# Steering_Wheel.net
KiCad netlist of a schematic drawn in Altium Designer
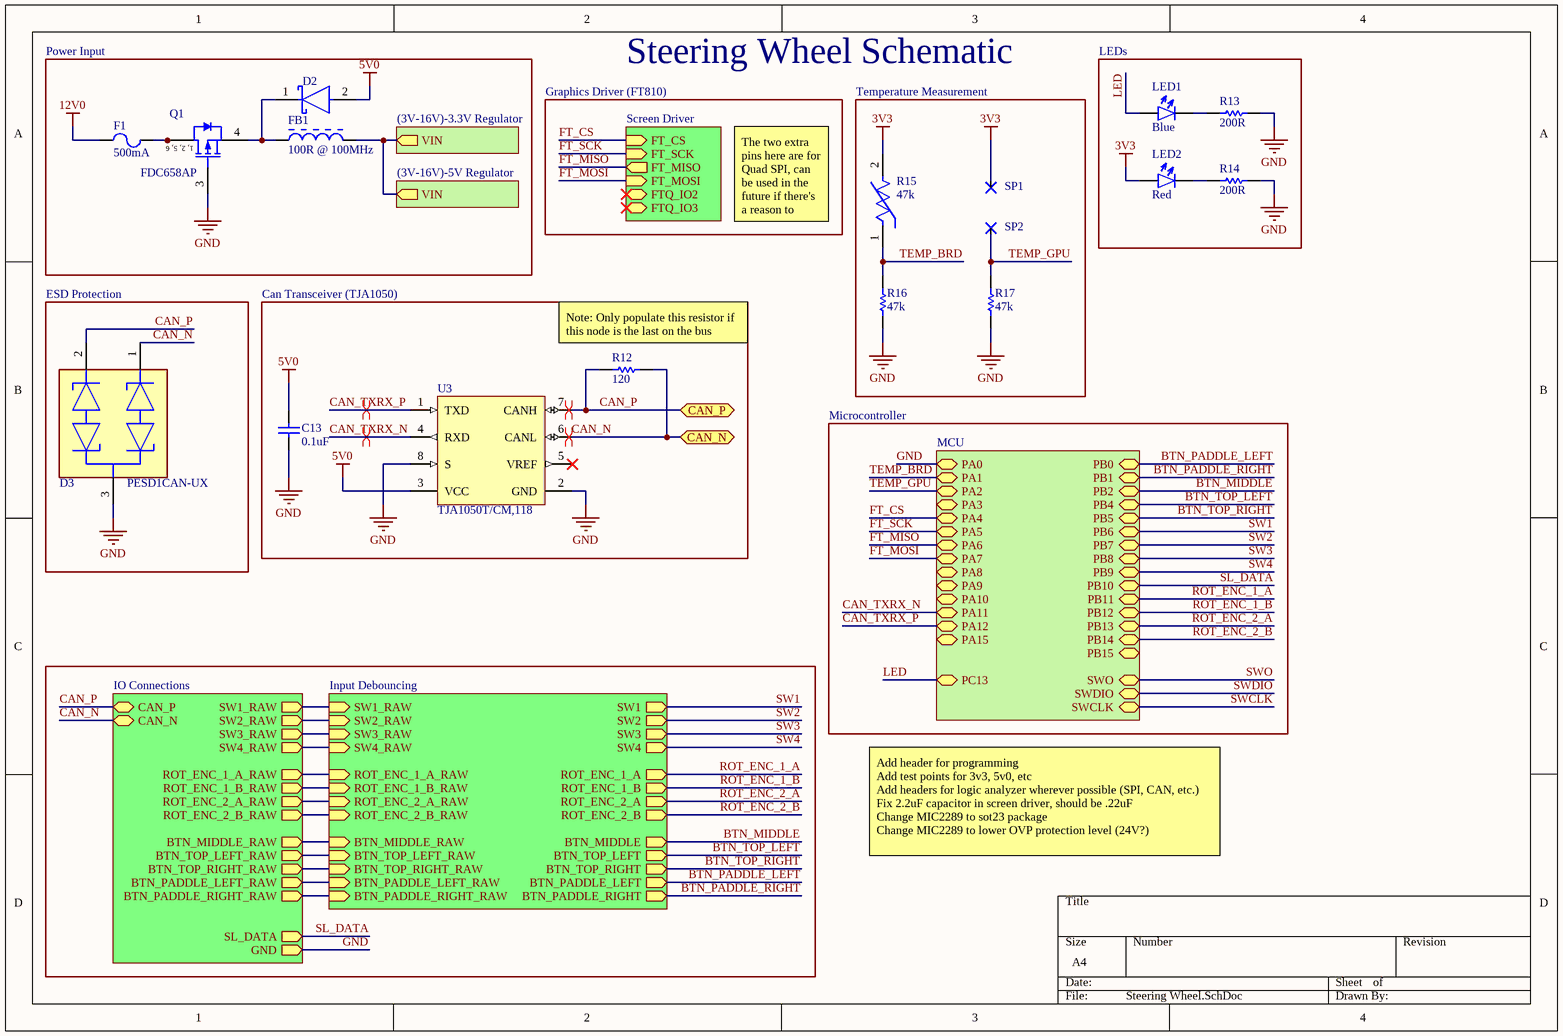
[diagram p0: Steering Wheel.SchDoc]

(export (version "E")
  (design (tool "Eeschema 10.0.6"))
  (components
    (comp (ref "C13")
      (value "0.1uF")
      (footprint "CAPC2013X88X50NL20T25")
      (fields
        (field (name "PART NUMBER") "C0805C104K5RACTU")
        (field (name "MANUFACTURER") "Kemet")
        (field (name "TOLERANCE") "10%")
      )
      (libsource (lib "Altium Content Vault") (part "CAP"))
    )
    (comp (ref "D2")
      (value "~")
      (footprint "FP-95400-MFG")
      (description "DIODE SCHOTTKY 40V 3A DO214AC")
      (fields
        (field (name "MANUFACTURER PART NUMBER") "SSA34-E3/61T")
        (field (name "OCTOPART") "https://octopart.com/ssa34-e3%2F61t-vishay-39552934")
      )
      (libsource (lib "Altium Content Vault") (part "1d6ec82d83fb6aee721767c19dac4b9"))
    )
    (comp (ref "D3")
      (value "PESD1CAN-UX")
      (footprint "FP-SOT323-MFG")
      (description "TVS DIODE 24V 50V SC70-3")
      (fields (field (name "MANUFACTURER") "Nexperia"))
      (libsource (lib "Altium Content Vault") (part "04d57993b6b7b0f5b3c95ba4f97dea0"))
    )
    (comp (ref "F1")
      (value "500mA")
      (footprint "LFUS-0452_V")
      (description "NANO2(R) Slo-Blo(R) Fuse, 0.5 A, 125 V, -55 to 125 degC, 2-Pin SMD, RoHS, Tape and Reel")
      (fields
        (field (name "MANUFACTURER") "Littelfuse")
        (field (name "MANUFACTURER PART NUMBER") "0452.500MRL")
      )
      (libsource (lib "Altium Content Vault") (part "FUSE-2"))
    )
    (comp (ref "FB1")
      (value "100R @ 100MHz")
      (footprint "MURA-BLM18PG_KG-B25-CHIP-2_V1")
      (fields
        (field (name "PARTNUMBER") "BLM18PG121SN1D")
        (field (name "MANUFACTURER") "Murata")
        (field (name "TOLERANCE") "25%")
      )
      (libsource (lib "Altium Content Vault") (part "MURA-FB-2"))
    )
    (comp (ref "LED1")
      (value "Blue")
      (footprint "Dummy Parts:0805")
      (libsource (lib "Dummy Parts") (part "LED"))
    )
    (comp (ref "LED2")
      (value "Red")
      (footprint "Dummy Parts:0805")
      (libsource (lib "Dummy Parts") (part "LED"))
    )
    (comp (ref "Q1")
      (value "FDC658AP")
      (footprint "FAIR-SOT23-6_V")
      (fields (field (name "MANUFACTURER") "Fairchild Semiconductor"))
      (libsource (lib "Altium Content Vault") (part "PEMOS-DDGSDD-6"))
    )
    (comp (ref "R12")
      (value "120")
      (footprint "RESC2013X70X40NL20T20")
      (description "Chip Resistor, 120 Ohm, +/- 1%, 0.125 W, -55 to 155 degC, 0805 (2012 Metric), RoHS, Tape and Reel")
      (fields
        (field (name "MANUFACTURER") "Panasonic")
        (field (name "MANUFACTURER PART NUMBER") "ERJ-6ENF1200V")
      )
      (libsource (lib "Altium Content Vault") (part "RES-2"))
    )
    (comp (ref "R13")
      (value "200R")
      (footprint "0805")
      (description "Resistor; Thick Film; Res 200 Ohms; Pwr-Rtg 0.125 W; Tol 1%; SMT; 0805; Cut Tape")
      (fields
        (field (name "MANUFACTURER") "Panasonic")
        (field (name "MANUFACTURER PART NUMBER") "ERJ-6ENF2000V")
      )
      (libsource (lib "Dummy Parts") (part "Resistor"))
    )
    (comp (ref "R14")
      (value "200R")
      (footprint "0805")
      (description "Resistor; Thick Film; Res 200 Ohms; Pwr-Rtg 0.125 W; Tol 1%; SMT; 0805; Cut Tape")
      (fields
        (field (name "MANUFACTURER") "Panasonic")
        (field (name "MANUFACTURER PART NUMBER") "ERJ-6ENF2000V")
      )
      (libsource (lib "Dummy Parts") (part "Resistor"))
    )
    (comp (ref "R15")
      (value "47k")
      (footprint "FP-NCP21-0_2-IPC_B")
      (description "THERMISTOR NTC 47KOHM 4050K 0805")
      (fields (field (name "TOLERANCE") "5%") (field (name "MANUFACTURER") "Murata"))
      (libsource (lib "Altium Content Vault") (part "3b148a6ebabc5fb4d708a66c052d352"))
    )
    (comp (ref "R16")
      (value "47k")
      (footprint "RESC2013X70X40ML20T20")
      (fields
        (field (name "MANUFACTURER") "Panasonic")
        (field (name "PART NUMBER") "ERJ6ENF4702V")
        (field (name "MANUFACTURER PART NUMBER") "ERJ-6ENF4702V")
      )
      (libsource (lib "Altium Content Vault") (part "RES"))
    )
    (comp (ref "R17")
      (value "47k")
      (footprint "RESC2013X70X40ML20T20")
      (fields
        (field (name "MANUFACTURER") "Panasonic")
        (field (name "PART NUMBER") "ERJ6ENF4702V")
        (field (name "MANUFACTURER PART NUMBER") "ERJ-6ENF4702V")
      )
      (libsource (lib "Altium Content Vault") (part "RES"))
    )
    (comp (ref "SP1")
      (value "Rectangular")
      (footprint "2.5x5mm")
      (libsource (lib "Solder Pads") (part "Rectangular"))
    )
    (comp (ref "SP2")
      (value "Rectangular")
      (footprint "2.5x5mm")
      (libsource (lib "Solder Pads") (part "Rectangular"))
    )
    (comp (ref "U3")
      (value "TJA1050T/CM,118")
      (footprint "NXP-SOT96-1_M")
      (fields (field (name "MANUFACTURER") "NXP Semiconductors"))
      (libsource (lib "Altium Content Vault") (part "NXP-TJA1050-8"))
    )
  )
  (nets
    (net (code "11") (name "/CAN_N") (class "Default")
      (node (ref "D3") (pin "1") (pinfunction "cathode_1_1") (pintype "passive"))
      (node (ref "R12") (pin "2") (pinfunction "2_2") (pintype "passive"))
      (node (ref "U3") (pin "6") (pinfunction "CANL_6") (pintype "bidirectional"))
    )
    (net (code "12") (name "/CAN_P") (class "Default")
      (node (ref "D3") (pin "2") (pinfunction "cathode_2_2") (pintype "passive"))
      (node (ref "R12") (pin "1") (pinfunction "1_1") (pintype "passive"))
      (node (ref "U3") (pin "7") (pinfunction "CANH_7") (pintype "bidirectional"))
    )
    (net (code "13") (name "/CAN_TXRX_N") (class "Default")
      (node (ref "U3") (pin "4") (pinfunction "RXD_4") (pintype "output"))
    )
    (net (code "14") (name "/CAN_TXRX_P") (class "Default")
      (node (ref "U3") (pin "1") (pinfunction "TXD_1") (pintype "input"))
    )
    (net (code "21") (name "/LED") (class "Default")
      (node (ref "LED1") (pin "1") (pinfunction "1_1") (pintype "passive"))
    )
    (net (code "48") (name "/TEMP_BRD") (class "Default")
      (node (ref "R15") (pin "1") (pinfunction "1_1") (pintype "passive"))
      (node (ref "R16") (pin "2") (pinfunction "2_2") (pintype "passive"))
    )
    (net (code "49") (name "/TEMP_GPU") (class "Default")
      (node (ref "R17") (pin "2") (pinfunction "2_2") (pintype "passive"))
      (node (ref "SP2") (pin "1") (pinfunction "1_1") (pintype "passive"))
    )
    (net (code "50") (name "/VIN") (class "Default")
      (node (ref "FB1") (pin "2") (pinfunction "2_2") (pintype "passive"))
    )
    (net (code "51") (name "3V3") (class "Default")
      (node (ref "LED2") (pin "1") (pinfunction "1_1") (pintype "passive"))
      (node (ref "R15") (pin "2") (pinfunction "2_2") (pintype "passive"))
      (node (ref "SP1") (pin "1") (pinfunction "1_1") (pintype "passive"))
    )
    (net (code "52") (name "5V0") (class "Default")
      (node (ref "C13") (pin "2") (pinfunction "2_2") (pintype "passive"))
      (node (ref "D2") (pin "2") (pinfunction "A_2") (pintype "passive"))
      (node (ref "U3") (pin "3") (pinfunction "VCC_3") (pintype "power_in"))
    )
    (net (code "53") (name "12V0") (class "Default")
      (node (ref "F1") (pin "1") (pinfunction "1_1") (pintype "passive"))
    )
    (net (code "54") (name "GND") (class "Default")
      (node (ref "C13") (pin "1") (pinfunction "1_1") (pintype "passive"))
      (node (ref "D3") (pin "3") (pinfunction "common_cathode_3") (pintype "passive"))
      (node (ref "Q1") (pin "3") (pinfunction "GATE_3") (pintype "passive"))
      (node (ref "R13") (pin "2") (pinfunction "2_2") (pintype "passive"))
      (node (ref "R14") (pin "2") (pinfunction "2_2") (pintype "passive"))
      (node (ref "R16") (pin "1") (pinfunction "1_1") (pintype "passive"))
      (node (ref "R17") (pin "1") (pinfunction "1_1") (pintype "passive"))
      (node (ref "U3") (pin "2") (pinfunction "GND_2") (pintype "power_in"))
      (node (ref "U3") (pin "8") (pinfunction "S_8") (pintype "input"))
    )
    (net (code "55") (name "Net-(D2-C)") (class "Default")
      (node (ref "D2") (pin "1") (pinfunction "C_1") (pintype "passive"))
      (node (ref "FB1") (pin "1") (pinfunction "1_1") (pintype "passive"))
      (node (ref "Q1") (pin "4") (pinfunction "SOURCE_4") (pintype "passive"))
    )
    (net (code "56") (name "Net-(F1-Pad2)") (class "Default")
      (node (ref "F1") (pin "2") (pinfunction "2_2") (pintype "passive"))
      (node (ref "Q1") (pin "1") (pinfunction "DRAIN_1") (pintype "passive"))
      (node (ref "Q1") (pin "2") (pinfunction "DRAIN_2") (pintype "passive"))
      (node (ref "Q1") (pin "5") (pinfunction "DRAIN_5") (pintype "passive"))
      (node (ref "Q1") (pin "6") (pinfunction "DRAIN_6") (pintype "passive"))
    )
    (net (code "57") (name "Net-(LED1-Pad2)") (class "Default")
      (node (ref "LED1") (pin "2") (pinfunction "2_2") (pintype "passive"))
      (node (ref "R13") (pin "1") (pinfunction "1_1") (pintype "passive"))
    )
    (net (code "58") (name "Net-(LED2-Pad2)") (class "Default")
      (node (ref "LED2") (pin "2") (pinfunction "2_2") (pintype "passive"))
      (node (ref "R14") (pin "1") (pinfunction "1_1") (pintype "passive"))
    )
    (net (code "59") (name "unconnected-(U3-VREF-Pad5)") (class "Default")
      (node (ref "U3") (pin "5") (pinfunction "VREF_5") (pintype "output+no_connect"))
    )
  )
)
